# current_sense.net
KiCad netlist of a schematic drawn in Altium Designer
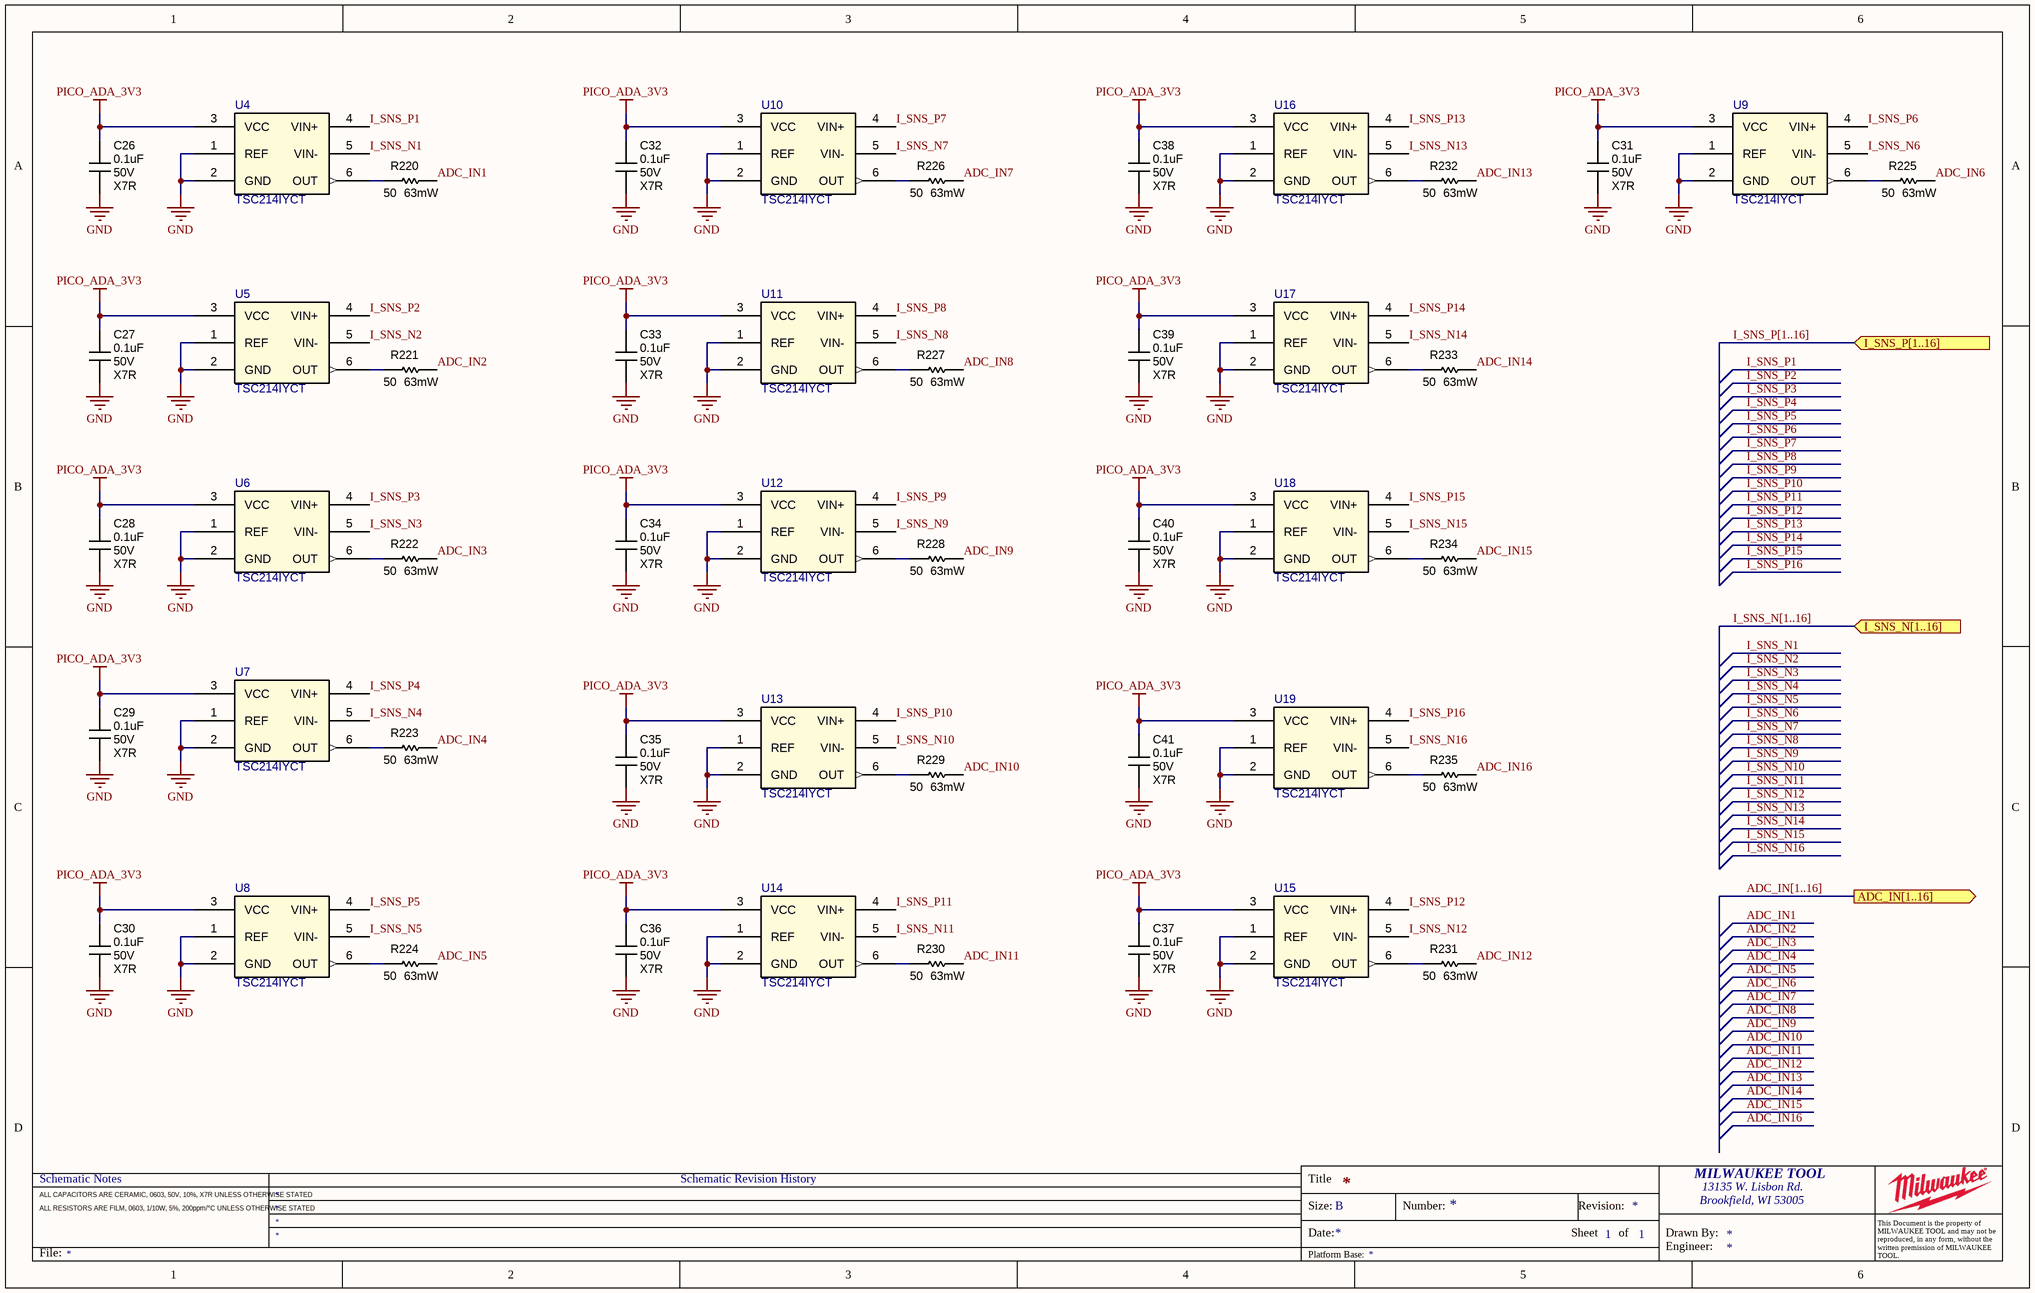
[diagram p0: current_sense.SchDoc]

(export (version "E")
  (design (tool "Eeschema 10.0.6"))
  (components
    (comp (ref "C26")
      (value "0.1uF")
      (footprint "CAPC1005X06N")
      (description "CAP CER SMD 0.1UF 50V X7R 0402")
      (fields
        (field (name "TOLERANCE") "10%")
        (field (name "MFR") "Murata Electronics")
        (field (name "VOLTAGE RATING") "50V")
        (field (name "TEMP COEFF") "X7R")
      )
      (libsource (lib "General_Library") (part "CMP-004-0076"))
    )
    (comp (ref "C27")
      (value "0.1uF")
      (footprint "CAPC1005X06N")
      (description "CAP CER SMD 0.1UF 50V X7R 0402")
      (fields
        (field (name "TOLERANCE") "10%")
        (field (name "MFR") "Murata Electronics")
        (field (name "VOLTAGE RATING") "50V")
        (field (name "TEMP COEFF") "X7R")
      )
      (libsource (lib "General_Library") (part "CMP-004-0076"))
    )
    (comp (ref "C28")
      (value "0.1uF")
      (footprint "CAPC1005X06N")
      (description "CAP CER SMD 0.1UF 50V X7R 0402")
      (fields
        (field (name "TOLERANCE") "10%")
        (field (name "MFR") "Murata Electronics")
        (field (name "VOLTAGE RATING") "50V")
        (field (name "TEMP COEFF") "X7R")
      )
      (libsource (lib "General_Library") (part "CMP-004-0076"))
    )
    (comp (ref "C29")
      (value "0.1uF")
      (footprint "CAPC1005X06N")
      (description "CAP CER SMD 0.1UF 50V X7R 0402")
      (fields
        (field (name "TOLERANCE") "10%")
        (field (name "MFR") "Murata Electronics")
        (field (name "VOLTAGE RATING") "50V")
        (field (name "TEMP COEFF") "X7R")
      )
      (libsource (lib "General_Library") (part "CMP-004-0076"))
    )
    (comp (ref "C30")
      (value "0.1uF")
      (footprint "CAPC1005X06N")
      (description "CAP CER SMD 0.1UF 50V X7R 0402")
      (fields
        (field (name "TOLERANCE") "10%")
        (field (name "MFR") "Murata Electronics")
        (field (name "VOLTAGE RATING") "50V")
        (field (name "TEMP COEFF") "X7R")
      )
      (libsource (lib "General_Library") (part "CMP-004-0076"))
    )
    (comp (ref "C31")
      (value "0.1uF")
      (footprint "CAPC1005X06N")
      (description "CAP CER SMD 0.1UF 50V X7R 0402")
      (fields
        (field (name "TOLERANCE") "10%")
        (field (name "MFR") "Murata Electronics")
        (field (name "VOLTAGE RATING") "50V")
        (field (name "TEMP COEFF") "X7R")
      )
      (libsource (lib "General_Library") (part "CMP-004-0076"))
    )
    (comp (ref "C32")
      (value "0.1uF")
      (footprint "CAPC1005X06N")
      (description "CAP CER SMD 0.1UF 50V X7R 0402")
      (fields
        (field (name "TOLERANCE") "10%")
        (field (name "MFR") "Murata Electronics")
        (field (name "VOLTAGE RATING") "50V")
        (field (name "TEMP COEFF") "X7R")
      )
      (libsource (lib "General_Library") (part "CMP-004-0076"))
    )
    (comp (ref "C33")
      (value "0.1uF")
      (footprint "CAPC1005X06N")
      (description "CAP CER SMD 0.1UF 50V X7R 0402")
      (fields
        (field (name "TOLERANCE") "10%")
        (field (name "MFR") "Murata Electronics")
        (field (name "VOLTAGE RATING") "50V")
        (field (name "TEMP COEFF") "X7R")
      )
      (libsource (lib "General_Library") (part "CMP-004-0076"))
    )
    (comp (ref "C34")
      (value "0.1uF")
      (footprint "CAPC1005X06N")
      (description "CAP CER SMD 0.1UF 50V X7R 0402")
      (fields
        (field (name "TOLERANCE") "10%")
        (field (name "MFR") "Murata Electronics")
        (field (name "VOLTAGE RATING") "50V")
        (field (name "TEMP COEFF") "X7R")
      )
      (libsource (lib "General_Library") (part "CMP-004-0076"))
    )
    (comp (ref "C35")
      (value "0.1uF")
      (footprint "CAPC1005X06N")
      (description "CAP CER SMD 0.1UF 50V X7R 0402")
      (fields
        (field (name "TOLERANCE") "10%")
        (field (name "MFR") "Murata Electronics")
        (field (name "VOLTAGE RATING") "50V")
        (field (name "TEMP COEFF") "X7R")
      )
      (libsource (lib "General_Library") (part "CMP-004-0076"))
    )
    (comp (ref "C36")
      (value "0.1uF")
      (footprint "CAPC1005X06N")
      (description "CAP CER SMD 0.1UF 50V X7R 0402")
      (fields
        (field (name "TOLERANCE") "10%")
        (field (name "MFR") "Murata Electronics")
        (field (name "VOLTAGE RATING") "50V")
        (field (name "TEMP COEFF") "X7R")
      )
      (libsource (lib "General_Library") (part "CMP-004-0076"))
    )
    (comp (ref "C37")
      (value "0.1uF")
      (footprint "CAPC1005X06N")
      (description "CAP CER SMD 0.1UF 50V X7R 0402")
      (fields
        (field (name "TOLERANCE") "10%")
        (field (name "MFR") "Murata Electronics")
        (field (name "VOLTAGE RATING") "50V")
        (field (name "TEMP COEFF") "X7R")
      )
      (libsource (lib "General_Library") (part "CMP-004-0076"))
    )
    (comp (ref "C38")
      (value "0.1uF")
      (footprint "CAPC1005X06N")
      (description "CAP CER SMD 0.1UF 50V X7R 0402")
      (fields
        (field (name "TOLERANCE") "10%")
        (field (name "MFR") "Murata Electronics")
        (field (name "VOLTAGE RATING") "50V")
        (field (name "TEMP COEFF") "X7R")
      )
      (libsource (lib "General_Library") (part "CMP-004-0076"))
    )
    (comp (ref "C39")
      (value "0.1uF")
      (footprint "CAPC1005X06N")
      (description "CAP CER SMD 0.1UF 50V X7R 0402")
      (fields
        (field (name "TOLERANCE") "10%")
        (field (name "MFR") "Murata Electronics")
        (field (name "VOLTAGE RATING") "50V")
        (field (name "TEMP COEFF") "X7R")
      )
      (libsource (lib "General_Library") (part "CMP-004-0076"))
    )
    (comp (ref "C40")
      (value "0.1uF")
      (footprint "CAPC1005X06N")
      (description "CAP CER SMD 0.1UF 50V X7R 0402")
      (fields
        (field (name "TOLERANCE") "10%")
        (field (name "MFR") "Murata Electronics")
        (field (name "VOLTAGE RATING") "50V")
        (field (name "TEMP COEFF") "X7R")
      )
      (libsource (lib "General_Library") (part "CMP-004-0076"))
    )
    (comp (ref "C41")
      (value "0.1uF")
      (footprint "CAPC1005X06N")
      (description "CAP CER SMD 0.1UF 50V X7R 0402")
      (fields
        (field (name "TOLERANCE") "10%")
        (field (name "MFR") "Murata Electronics")
        (field (name "VOLTAGE RATING") "50V")
        (field (name "TEMP COEFF") "X7R")
      )
      (libsource (lib "General_Library") (part "CMP-004-0076"))
    )
    (comp (ref "R220")
      (value "50")
      (footprint "RESC1005X04N")
      (description "RES SMD 50R OHM 1% 1/16W 0402")
      (fields
        (field (name "TOLERANCE") "1%")
        (field (name "MFR") "KOA Speer Electronics")
        (field (name "WATTAGE") "63mW")
      )
      (libsource (lib "General_Library") (part "CMP-025-0174"))
    )
    (comp (ref "R221")
      (value "50")
      (footprint "RESC1005X04N")
      (description "RES SMD 50R OHM 1% 1/16W 0402")
      (fields
        (field (name "TOLERANCE") "1%")
        (field (name "MFR") "KOA Speer Electronics")
        (field (name "WATTAGE") "63mW")
      )
      (libsource (lib "General_Library") (part "CMP-025-0174"))
    )
    (comp (ref "R222")
      (value "50")
      (footprint "RESC1005X04N")
      (description "RES SMD 50R OHM 1% 1/16W 0402")
      (fields
        (field (name "TOLERANCE") "1%")
        (field (name "MFR") "KOA Speer Electronics")
        (field (name "WATTAGE") "63mW")
      )
      (libsource (lib "General_Library") (part "CMP-025-0174"))
    )
    (comp (ref "R223")
      (value "50")
      (footprint "RESC1005X04N")
      (description "RES SMD 50R OHM 1% 1/16W 0402")
      (fields
        (field (name "TOLERANCE") "1%")
        (field (name "MFR") "KOA Speer Electronics")
        (field (name "WATTAGE") "63mW")
      )
      (libsource (lib "General_Library") (part "CMP-025-0174"))
    )
    (comp (ref "R224")
      (value "50")
      (footprint "RESC1005X04N")
      (description "RES SMD 50R OHM 1% 1/16W 0402")
      (fields
        (field (name "TOLERANCE") "1%")
        (field (name "MFR") "KOA Speer Electronics")
        (field (name "WATTAGE") "63mW")
      )
      (libsource (lib "General_Library") (part "CMP-025-0174"))
    )
    (comp (ref "R225")
      (value "50")
      (footprint "RESC1005X04N")
      (description "RES SMD 50R OHM 1% 1/16W 0402")
      (fields
        (field (name "TOLERANCE") "1%")
        (field (name "MFR") "KOA Speer Electronics")
        (field (name "WATTAGE") "63mW")
      )
      (libsource (lib "General_Library") (part "CMP-025-0174"))
    )
    (comp (ref "R226")
      (value "50")
      (footprint "RESC1005X04N")
      (description "RES SMD 50R OHM 1% 1/16W 0402")
      (fields
        (field (name "TOLERANCE") "1%")
        (field (name "MFR") "KOA Speer Electronics")
        (field (name "WATTAGE") "63mW")
      )
      (libsource (lib "General_Library") (part "CMP-025-0174"))
    )
    (comp (ref "R227")
      (value "50")
      (footprint "RESC1005X04N")
      (description "RES SMD 50R OHM 1% 1/16W 0402")
      (fields
        (field (name "TOLERANCE") "1%")
        (field (name "MFR") "KOA Speer Electronics")
        (field (name "WATTAGE") "63mW")
      )
      (libsource (lib "General_Library") (part "CMP-025-0174"))
    )
    (comp (ref "R228")
      (value "50")
      (footprint "RESC1005X04N")
      (description "RES SMD 50R OHM 1% 1/16W 0402")
      (fields
        (field (name "TOLERANCE") "1%")
        (field (name "MFR") "KOA Speer Electronics")
        (field (name "WATTAGE") "63mW")
      )
      (libsource (lib "General_Library") (part "CMP-025-0174"))
    )
    (comp (ref "R229")
      (value "50")
      (footprint "RESC1005X04N")
      (description "RES SMD 50R OHM 1% 1/16W 0402")
      (fields
        (field (name "TOLERANCE") "1%")
        (field (name "MFR") "KOA Speer Electronics")
        (field (name "WATTAGE") "63mW")
      )
      (libsource (lib "General_Library") (part "CMP-025-0174"))
    )
    (comp (ref "R230")
      (value "50")
      (footprint "RESC1005X04N")
      (description "RES SMD 50R OHM 1% 1/16W 0402")
      (fields
        (field (name "TOLERANCE") "1%")
        (field (name "MFR") "KOA Speer Electronics")
        (field (name "WATTAGE") "63mW")
      )
      (libsource (lib "General_Library") (part "CMP-025-0174"))
    )
    (comp (ref "R231")
      (value "50")
      (footprint "RESC1005X04N")
      (description "RES SMD 50R OHM 1% 1/16W 0402")
      (fields
        (field (name "TOLERANCE") "1%")
        (field (name "MFR") "KOA Speer Electronics")
        (field (name "WATTAGE") "63mW")
      )
      (libsource (lib "General_Library") (part "CMP-025-0174"))
    )
    (comp (ref "R232")
      (value "50")
      (footprint "RESC1005X04N")
      (description "RES SMD 50R OHM 1% 1/16W 0402")
      (fields
        (field (name "TOLERANCE") "1%")
        (field (name "MFR") "KOA Speer Electronics")
        (field (name "WATTAGE") "63mW")
      )
      (libsource (lib "General_Library") (part "CMP-025-0174"))
    )
    (comp (ref "R233")
      (value "50")
      (footprint "RESC1005X04N")
      (description "RES SMD 50R OHM 1% 1/16W 0402")
      (fields
        (field (name "TOLERANCE") "1%")
        (field (name "MFR") "KOA Speer Electronics")
        (field (name "WATTAGE") "63mW")
      )
      (libsource (lib "General_Library") (part "CMP-025-0174"))
    )
    (comp (ref "R234")
      (value "50")
      (footprint "RESC1005X04N")
      (description "RES SMD 50R OHM 1% 1/16W 0402")
      (fields
        (field (name "TOLERANCE") "1%")
        (field (name "MFR") "KOA Speer Electronics")
        (field (name "WATTAGE") "63mW")
      )
      (libsource (lib "General_Library") (part "CMP-025-0174"))
    )
    (comp (ref "R235")
      (value "50")
      (footprint "RESC1005X04N")
      (description "RES SMD 50R OHM 1% 1/16W 0402")
      (fields
        (field (name "TOLERANCE") "1%")
        (field (name "MFR") "KOA Speer Electronics")
        (field (name "WATTAGE") "63mW")
      )
      (libsource (lib "General_Library") (part "CMP-025-0174"))
    )
    (comp (ref "U4")
      (value "TSC214IYCT")
      (footprint "Footprints:SOT65P210X110-6N")
      (description "IC CURR SENSE 1 CIRCUIT SC70-6")
      (fields (field (name "MFR") "STMicroelectronics"))
      (libsource (lib "Symbols") (part "CMP-017-0113"))
    )
    (comp (ref "U5")
      (value "TSC214IYCT")
      (footprint "Footprints:SOT65P210X110-6N")
      (description "IC CURR SENSE 1 CIRCUIT SC70-6")
      (fields (field (name "MFR") "STMicroelectronics"))
      (libsource (lib "Symbols") (part "CMP-017-0113"))
    )
    (comp (ref "U6")
      (value "TSC214IYCT")
      (footprint "Footprints:SOT65P210X110-6N")
      (description "IC CURR SENSE 1 CIRCUIT SC70-6")
      (fields (field (name "MFR") "STMicroelectronics"))
      (libsource (lib "Symbols") (part "CMP-017-0113"))
    )
    (comp (ref "U7")
      (value "TSC214IYCT")
      (footprint "Footprints:SOT65P210X110-6N")
      (description "IC CURR SENSE 1 CIRCUIT SC70-6")
      (fields (field (name "MFR") "STMicroelectronics"))
      (libsource (lib "Symbols") (part "CMP-017-0113"))
    )
    (comp (ref "U8")
      (value "TSC214IYCT")
      (footprint "Footprints:SOT65P210X110-6N")
      (description "IC CURR SENSE 1 CIRCUIT SC70-6")
      (fields (field (name "MFR") "STMicroelectronics"))
      (libsource (lib "Symbols") (part "CMP-017-0113"))
    )
    (comp (ref "U9")
      (value "TSC214IYCT")
      (footprint "Footprints:SOT65P210X110-6N")
      (description "IC CURR SENSE 1 CIRCUIT SC70-6")
      (fields (field (name "MFR") "STMicroelectronics"))
      (libsource (lib "Symbols") (part "CMP-017-0113"))
    )
    (comp (ref "U10")
      (value "TSC214IYCT")
      (footprint "Footprints:SOT65P210X110-6N")
      (description "IC CURR SENSE 1 CIRCUIT SC70-6")
      (fields (field (name "MFR") "STMicroelectronics"))
      (libsource (lib "Symbols") (part "CMP-017-0113"))
    )
    (comp (ref "U11")
      (value "TSC214IYCT")
      (footprint "Footprints:SOT65P210X110-6N")
      (description "IC CURR SENSE 1 CIRCUIT SC70-6")
      (fields (field (name "MFR") "STMicroelectronics"))
      (libsource (lib "Symbols") (part "CMP-017-0113"))
    )
    (comp (ref "U12")
      (value "TSC214IYCT")
      (footprint "Footprints:SOT65P210X110-6N")
      (description "IC CURR SENSE 1 CIRCUIT SC70-6")
      (fields (field (name "MFR") "STMicroelectronics"))
      (libsource (lib "Symbols") (part "CMP-017-0113"))
    )
    (comp (ref "U13")
      (value "TSC214IYCT")
      (footprint "Footprints:SOT65P210X110-6N")
      (description "IC CURR SENSE 1 CIRCUIT SC70-6")
      (fields (field (name "MFR") "STMicroelectronics"))
      (libsource (lib "Symbols") (part "CMP-017-0113"))
    )
    (comp (ref "U14")
      (value "TSC214IYCT")
      (footprint "Footprints:SOT65P210X110-6N")
      (description "IC CURR SENSE 1 CIRCUIT SC70-6")
      (fields (field (name "MFR") "STMicroelectronics"))
      (libsource (lib "Symbols") (part "CMP-017-0113"))
    )
    (comp (ref "U15")
      (value "TSC214IYCT")
      (footprint "Footprints:SOT65P210X110-6N")
      (description "IC CURR SENSE 1 CIRCUIT SC70-6")
      (fields (field (name "MFR") "STMicroelectronics"))
      (libsource (lib "Symbols") (part "CMP-017-0113"))
    )
    (comp (ref "U16")
      (value "TSC214IYCT")
      (footprint "Footprints:SOT65P210X110-6N")
      (description "IC CURR SENSE 1 CIRCUIT SC70-6")
      (fields (field (name "MFR") "STMicroelectronics"))
      (libsource (lib "Symbols") (part "CMP-017-0113"))
    )
    (comp (ref "U17")
      (value "TSC214IYCT")
      (footprint "Footprints:SOT65P210X110-6N")
      (description "IC CURR SENSE 1 CIRCUIT SC70-6")
      (fields (field (name "MFR") "STMicroelectronics"))
      (libsource (lib "Symbols") (part "CMP-017-0113"))
    )
    (comp (ref "U18")
      (value "TSC214IYCT")
      (footprint "Footprints:SOT65P210X110-6N")
      (description "IC CURR SENSE 1 CIRCUIT SC70-6")
      (fields (field (name "MFR") "STMicroelectronics"))
      (libsource (lib "Symbols") (part "CMP-017-0113"))
    )
    (comp (ref "U19")
      (value "TSC214IYCT")
      (footprint "Footprints:SOT65P210X110-6N")
      (description "IC CURR SENSE 1 CIRCUIT SC70-6")
      (fields (field (name "MFR") "STMicroelectronics"))
      (libsource (lib "Symbols") (part "CMP-017-0113"))
    )
  )
  (nets
    (net (code "1") (name "/ADC_IN1") (class "Default")
      (node (ref "R220") (pin "2") (pinfunction "2_2") (pintype "passive"))
    )
    (net (code "2") (name "/ADC_IN2") (class "Default")
      (node (ref "R221") (pin "2") (pinfunction "2_2") (pintype "passive"))
    )
    (net (code "3") (name "/ADC_IN3") (class "Default")
      (node (ref "R222") (pin "2") (pinfunction "2_2") (pintype "passive"))
    )
    (net (code "4") (name "/ADC_IN4") (class "Default")
      (node (ref "R223") (pin "2") (pinfunction "2_2") (pintype "passive"))
    )
    (net (code "5") (name "/ADC_IN5") (class "Default")
      (node (ref "R224") (pin "2") (pinfunction "2_2") (pintype "passive"))
    )
    (net (code "6") (name "/ADC_IN6") (class "Default")
      (node (ref "R225") (pin "2") (pinfunction "2_2") (pintype "passive"))
    )
    (net (code "7") (name "/ADC_IN7") (class "Default")
      (node (ref "R226") (pin "2") (pinfunction "2_2") (pintype "passive"))
    )
    (net (code "8") (name "/ADC_IN8") (class "Default")
      (node (ref "R227") (pin "2") (pinfunction "2_2") (pintype "passive"))
    )
    (net (code "9") (name "/ADC_IN9") (class "Default")
      (node (ref "R228") (pin "2") (pinfunction "2_2") (pintype "passive"))
    )
    (net (code "10") (name "/ADC_IN10") (class "Default")
      (node (ref "R229") (pin "2") (pinfunction "2_2") (pintype "passive"))
    )
    (net (code "11") (name "/ADC_IN11") (class "Default")
      (node (ref "R230") (pin "2") (pinfunction "2_2") (pintype "passive"))
    )
    (net (code "12") (name "/ADC_IN12") (class "Default")
      (node (ref "R231") (pin "2") (pinfunction "2_2") (pintype "passive"))
    )
    (net (code "13") (name "/ADC_IN13") (class "Default")
      (node (ref "R232") (pin "2") (pinfunction "2_2") (pintype "passive"))
    )
    (net (code "14") (name "/ADC_IN14") (class "Default")
      (node (ref "R233") (pin "2") (pinfunction "2_2") (pintype "passive"))
    )
    (net (code "15") (name "/ADC_IN15") (class "Default")
      (node (ref "R234") (pin "2") (pinfunction "2_2") (pintype "passive"))
    )
    (net (code "16") (name "/ADC_IN16") (class "Default")
      (node (ref "R235") (pin "2") (pinfunction "2_2") (pintype "passive"))
    )
    (net (code "18") (name "/I_SNS_N1") (class "Default")
      (node (ref "U4") (pin "5") (pinfunction "VIN-_5") (pintype "passive"))
    )
    (net (code "19") (name "/I_SNS_N2") (class "Default")
      (node (ref "U5") (pin "5") (pinfunction "VIN-_5") (pintype "passive"))
    )
    (net (code "20") (name "/I_SNS_N3") (class "Default")
      (node (ref "U6") (pin "5") (pinfunction "VIN-_5") (pintype "passive"))
    )
    (net (code "21") (name "/I_SNS_N4") (class "Default")
      (node (ref "U7") (pin "5") (pinfunction "VIN-_5") (pintype "passive"))
    )
    (net (code "22") (name "/I_SNS_N5") (class "Default")
      (node (ref "U8") (pin "5") (pinfunction "VIN-_5") (pintype "passive"))
    )
    (net (code "23") (name "/I_SNS_N6") (class "Default")
      (node (ref "U9") (pin "5") (pinfunction "VIN-_5") (pintype "passive"))
    )
    (net (code "24") (name "/I_SNS_N7") (class "Default")
      (node (ref "U10") (pin "5") (pinfunction "VIN-_5") (pintype "passive"))
    )
    (net (code "25") (name "/I_SNS_N8") (class "Default")
      (node (ref "U11") (pin "5") (pinfunction "VIN-_5") (pintype "passive"))
    )
    (net (code "26") (name "/I_SNS_N9") (class "Default")
      (node (ref "U12") (pin "5") (pinfunction "VIN-_5") (pintype "passive"))
    )
    (net (code "27") (name "/I_SNS_N10") (class "Default")
      (node (ref "U13") (pin "5") (pinfunction "VIN-_5") (pintype "passive"))
    )
    (net (code "28") (name "/I_SNS_N11") (class "Default")
      (node (ref "U14") (pin "5") (pinfunction "VIN-_5") (pintype "passive"))
    )
    (net (code "29") (name "/I_SNS_N12") (class "Default")
      (node (ref "U15") (pin "5") (pinfunction "VIN-_5") (pintype "passive"))
    )
    (net (code "30") (name "/I_SNS_N13") (class "Default")
      (node (ref "U16") (pin "5") (pinfunction "VIN-_5") (pintype "passive"))
    )
    (net (code "31") (name "/I_SNS_N14") (class "Default")
      (node (ref "U17") (pin "5") (pinfunction "VIN-_5") (pintype "passive"))
    )
    (net (code "32") (name "/I_SNS_N15") (class "Default")
      (node (ref "U18") (pin "5") (pinfunction "VIN-_5") (pintype "passive"))
    )
    (net (code "33") (name "/I_SNS_N16") (class "Default")
      (node (ref "U19") (pin "5") (pinfunction "VIN-_5") (pintype "passive"))
    )
    (net (code "35") (name "/I_SNS_P1") (class "Default")
      (node (ref "U4") (pin "4") (pinfunction "VIN+_4") (pintype "passive"))
    )
    (net (code "36") (name "/I_SNS_P2") (class "Default")
      (node (ref "U5") (pin "4") (pinfunction "VIN+_4") (pintype "passive"))
    )
    (net (code "37") (name "/I_SNS_P3") (class "Default")
      (node (ref "U6") (pin "4") (pinfunction "VIN+_4") (pintype "passive"))
    )
    (net (code "38") (name "/I_SNS_P4") (class "Default")
      (node (ref "U7") (pin "4") (pinfunction "VIN+_4") (pintype "passive"))
    )
    (net (code "39") (name "/I_SNS_P5") (class "Default")
      (node (ref "U8") (pin "4") (pinfunction "VIN+_4") (pintype "passive"))
    )
    (net (code "40") (name "/I_SNS_P6") (class "Default")
      (node (ref "U9") (pin "4") (pinfunction "VIN+_4") (pintype "passive"))
    )
    (net (code "41") (name "/I_SNS_P7") (class "Default")
      (node (ref "U10") (pin "4") (pinfunction "VIN+_4") (pintype "passive"))
    )
    (net (code "42") (name "/I_SNS_P8") (class "Default")
      (node (ref "U11") (pin "4") (pinfunction "VIN+_4") (pintype "passive"))
    )
    (net (code "43") (name "/I_SNS_P9") (class "Default")
      (node (ref "U12") (pin "4") (pinfunction "VIN+_4") (pintype "passive"))
    )
    (net (code "44") (name "/I_SNS_P10") (class "Default")
      (node (ref "U13") (pin "4") (pinfunction "VIN+_4") (pintype "passive"))
    )
    (net (code "45") (name "/I_SNS_P11") (class "Default")
      (node (ref "U14") (pin "4") (pinfunction "VIN+_4") (pintype "passive"))
    )
    (net (code "46") (name "/I_SNS_P12") (class "Default")
      (node (ref "U15") (pin "4") (pinfunction "VIN+_4") (pintype "passive"))
    )
    (net (code "47") (name "/I_SNS_P13") (class "Default")
      (node (ref "U16") (pin "4") (pinfunction "VIN+_4") (pintype "passive"))
    )
    (net (code "48") (name "/I_SNS_P14") (class "Default")
      (node (ref "U17") (pin "4") (pinfunction "VIN+_4") (pintype "passive"))
    )
    (net (code "49") (name "/I_SNS_P15") (class "Default")
      (node (ref "U18") (pin "4") (pinfunction "VIN+_4") (pintype "passive"))
    )
    (net (code "50") (name "/I_SNS_P16") (class "Default")
      (node (ref "U19") (pin "4") (pinfunction "VIN+_4") (pintype "passive"))
    )
    (net (code "52") (name "GND") (class "Default")
      (node (ref "C26") (pin "2") (pinfunction "2_2") (pintype "passive"))
      (node (ref "C27") (pin "2") (pinfunction "2_2") (pintype "passive"))
      (node (ref "C28") (pin "2") (pinfunction "2_2") (pintype "passive"))
      (node (ref "C29") (pin "2") (pinfunction "2_2") (pintype "passive"))
      (node (ref "C30") (pin "2") (pinfunction "2_2") (pintype "passive"))
      (node (ref "C31") (pin "2") (pinfunction "2_2") (pintype "passive"))
      (node (ref "C32") (pin "2") (pinfunction "2_2") (pintype "passive"))
      (node (ref "C33") (pin "2") (pinfunction "2_2") (pintype "passive"))
      (node (ref "C34") (pin "2") (pinfunction "2_2") (pintype "passive"))
      (node (ref "C35") (pin "2") (pinfunction "2_2") (pintype "passive"))
      (node (ref "C36") (pin "2") (pinfunction "2_2") (pintype "passive"))
      (node (ref "C37") (pin "2") (pinfunction "2_2") (pintype "passive"))
      (node (ref "C38") (pin "2") (pinfunction "2_2") (pintype "passive"))
      (node (ref "C39") (pin "2") (pinfunction "2_2") (pintype "passive"))
      (node (ref "C40") (pin "2") (pinfunction "2_2") (pintype "passive"))
      (node (ref "C41") (pin "2") (pinfunction "2_2") (pintype "passive"))
      (node (ref "U10") (pin "1") (pinfunction "REF_1") (pintype "passive"))
      (node (ref "U10") (pin "2") (pinfunction "GND_2") (pintype "power_in"))
      (node (ref "U11") (pin "1") (pinfunction "REF_1") (pintype "passive"))
      (node (ref "U11") (pin "2") (pinfunction "GND_2") (pintype "power_in"))
      (node (ref "U12") (pin "1") (pinfunction "REF_1") (pintype "passive"))
      (node (ref "U12") (pin "2") (pinfunction "GND_2") (pintype "power_in"))
      (node (ref "U13") (pin "1") (pinfunction "REF_1") (pintype "passive"))
      (node (ref "U13") (pin "2") (pinfunction "GND_2") (pintype "power_in"))
      (node (ref "U14") (pin "1") (pinfunction "REF_1") (pintype "passive"))
      (node (ref "U14") (pin "2") (pinfunction "GND_2") (pintype "power_in"))
      (node (ref "U15") (pin "1") (pinfunction "REF_1") (pintype "passive"))
      (node (ref "U15") (pin "2") (pinfunction "GND_2") (pintype "power_in"))
      (node (ref "U16") (pin "1") (pinfunction "REF_1") (pintype "passive"))
      (node (ref "U16") (pin "2") (pinfunction "GND_2") (pintype "power_in"))
      (node (ref "U17") (pin "1") (pinfunction "REF_1") (pintype "passive"))
      (node (ref "U17") (pin "2") (pinfunction "GND_2") (pintype "power_in"))
      (node (ref "U18") (pin "1") (pinfunction "REF_1") (pintype "passive"))
      (node (ref "U18") (pin "2") (pinfunction "GND_2") (pintype "power_in"))
      (node (ref "U19") (pin "1") (pinfunction "REF_1") (pintype "passive"))
      (node (ref "U19") (pin "2") (pinfunction "GND_2") (pintype "power_in"))
      (node (ref "U4") (pin "1") (pinfunction "REF_1") (pintype "passive"))
      (node (ref "U4") (pin "2") (pinfunction "GND_2") (pintype "power_in"))
      (node (ref "U5") (pin "1") (pinfunction "REF_1") (pintype "passive"))
      (node (ref "U5") (pin "2") (pinfunction "GND_2") (pintype "power_in"))
      (node (ref "U6") (pin "1") (pinfunction "REF_1") (pintype "passive"))
      (node (ref "U6") (pin "2") (pinfunction "GND_2") (pintype "power_in"))
      (node (ref "U7") (pin "1") (pinfunction "REF_1") (pintype "passive"))
      (node (ref "U7") (pin "2") (pinfunction "GND_2") (pintype "power_in"))
      (node (ref "U8") (pin "1") (pinfunction "REF_1") (pintype "passive"))
      (node (ref "U8") (pin "2") (pinfunction "GND_2") (pintype "power_in"))
      (node (ref "U9") (pin "1") (pinfunction "REF_1") (pintype "passive"))
      (node (ref "U9") (pin "2") (pinfunction "GND_2") (pintype "power_in"))
    )
    (net (code "53") (name "Net-(U4-OUT)") (class "Default")
      (node (ref "R220") (pin "1") (pinfunction "1_1") (pintype "passive"))
      (node (ref "U4") (pin "6") (pinfunction "OUT_6") (pintype "output"))
    )
    (net (code "54") (name "Net-(U5-OUT)") (class "Default")
      (node (ref "R221") (pin "1") (pinfunction "1_1") (pintype "passive"))
      (node (ref "U5") (pin "6") (pinfunction "OUT_6") (pintype "output"))
    )
    (net (code "55") (name "Net-(U6-OUT)") (class "Default")
      (node (ref "R222") (pin "1") (pinfunction "1_1") (pintype "passive"))
      (node (ref "U6") (pin "6") (pinfunction "OUT_6") (pintype "output"))
    )
    (net (code "56") (name "Net-(U7-OUT)") (class "Default")
      (node (ref "R223") (pin "1") (pinfunction "1_1") (pintype "passive"))
      (node (ref "U7") (pin "6") (pinfunction "OUT_6") (pintype "output"))
    )
    (net (code "57") (name "Net-(U8-OUT)") (class "Default")
      (node (ref "R224") (pin "1") (pinfunction "1_1") (pintype "passive"))
      (node (ref "U8") (pin "6") (pinfunction "OUT_6") (pintype "output"))
    )
    (net (code "58") (name "Net-(U9-OUT)") (class "Default")
      (node (ref "R225") (pin "1") (pinfunction "1_1") (pintype "passive"))
      (node (ref "U9") (pin "6") (pinfunction "OUT_6") (pintype "output"))
    )
    (net (code "59") (name "Net-(U10-OUT)") (class "Default")
      (node (ref "R226") (pin "1") (pinfunction "1_1") (pintype "passive"))
      (node (ref "U10") (pin "6") (pinfunction "OUT_6") (pintype "output"))
    )
    (net (code "60") (name "Net-(U11-OUT)") (class "Default")
      (node (ref "R227") (pin "1") (pinfunction "1_1") (pintype "passive"))
      (node (ref "U11") (pin "6") (pinfunction "OUT_6") (pintype "output"))
    )
    (net (code "61") (name "Net-(U12-OUT)") (class "Default")
      (node (ref "R228") (pin "1") (pinfunction "1_1") (pintype "passive"))
      (node (ref "U12") (pin "6") (pinfunction "OUT_6") (pintype "output"))
    )
    (net (code "62") (name "Net-(U13-OUT)") (class "Default")
      (node (ref "R229") (pin "1") (pinfunction "1_1") (pintype "passive"))
      (node (ref "U13") (pin "6") (pinfunction "OUT_6") (pintype "output"))
    )
    (net (code "63") (name "Net-(U14-OUT)") (class "Default")
      (node (ref "R230") (pin "1") (pinfunction "1_1") (pintype "passive"))
      (node (ref "U14") (pin "6") (pinfunction "OUT_6") (pintype "output"))
    )
    (net (code "64") (name "Net-(U15-OUT)") (class "Default")
      (node (ref "R231") (pin "1") (pinfunction "1_1") (pintype "passive"))
      (node (ref "U15") (pin "6") (pinfunction "OUT_6") (pintype "output"))
    )
    (net (code "65") (name "Net-(U16-OUT)") (class "Default")
      (node (ref "R232") (pin "1") (pinfunction "1_1") (pintype "passive"))
      (node (ref "U16") (pin "6") (pinfunction "OUT_6") (pintype "output"))
    )
    (net (code "66") (name "Net-(U17-OUT)") (class "Default")
      (node (ref "R233") (pin "1") (pinfunction "1_1") (pintype "passive"))
      (node (ref "U17") (pin "6") (pinfunction "OUT_6") (pintype "output"))
    )
    (net (code "67") (name "Net-(U18-OUT)") (class "Default")
      (node (ref "R234") (pin "1") (pinfunction "1_1") (pintype "passive"))
      (node (ref "U18") (pin "6") (pinfunction "OUT_6") (pintype "output"))
    )
    (net (code "68") (name "Net-(U19-OUT)") (class "Default")
      (node (ref "R235") (pin "1") (pinfunction "1_1") (pintype "passive"))
      (node (ref "U19") (pin "6") (pinfunction "OUT_6") (pintype "output"))
    )
    (net (code "69") (name "PICO_ADA_3V3") (class "Default")
      (node (ref "C26") (pin "1") (pinfunction "1_1") (pintype "passive"))
      (node (ref "C27") (pin "1") (pinfunction "1_1") (pintype "passive"))
      (node (ref "C28") (pin "1") (pinfunction "1_1") (pintype "passive"))
      (node (ref "C29") (pin "1") (pinfunction "1_1") (pintype "passive"))
      (node (ref "C30") (pin "1") (pinfunction "1_1") (pintype "passive"))
      (node (ref "C31") (pin "1") (pinfunction "1_1") (pintype "passive"))
      (node (ref "C32") (pin "1") (pinfunction "1_1") (pintype "passive"))
      (node (ref "C33") (pin "1") (pinfunction "1_1") (pintype "passive"))
      (node (ref "C34") (pin "1") (pinfunction "1_1") (pintype "passive"))
      (node (ref "C35") (pin "1") (pinfunction "1_1") (pintype "passive"))
      (node (ref "C36") (pin "1") (pinfunction "1_1") (pintype "passive"))
      (node (ref "C37") (pin "1") (pinfunction "1_1") (pintype "passive"))
      (node (ref "C38") (pin "1") (pinfunction "1_1") (pintype "passive"))
      (node (ref "C39") (pin "1") (pinfunction "1_1") (pintype "passive"))
      (node (ref "C40") (pin "1") (pinfunction "1_1") (pintype "passive"))
      (node (ref "C41") (pin "1") (pinfunction "1_1") (pintype "passive"))
      (node (ref "U10") (pin "3") (pinfunction "VCC_3") (pintype "power_in"))
      (node (ref "U11") (pin "3") (pinfunction "VCC_3") (pintype "power_in"))
      (node (ref "U12") (pin "3") (pinfunction "VCC_3") (pintype "power_in"))
      (node (ref "U13") (pin "3") (pinfunction "VCC_3") (pintype "power_in"))
      (node (ref "U14") (pin "3") (pinfunction "VCC_3") (pintype "power_in"))
      (node (ref "U15") (pin "3") (pinfunction "VCC_3") (pintype "power_in"))
      (node (ref "U16") (pin "3") (pinfunction "VCC_3") (pintype "power_in"))
      (node (ref "U17") (pin "3") (pinfunction "VCC_3") (pintype "power_in"))
      (node (ref "U18") (pin "3") (pinfunction "VCC_3") (pintype "power_in"))
      (node (ref "U19") (pin "3") (pinfunction "VCC_3") (pintype "power_in"))
      (node (ref "U4") (pin "3") (pinfunction "VCC_3") (pintype "power_in"))
      (node (ref "U5") (pin "3") (pinfunction "VCC_3") (pintype "power_in"))
      (node (ref "U6") (pin "3") (pinfunction "VCC_3") (pintype "power_in"))
      (node (ref "U7") (pin "3") (pinfunction "VCC_3") (pintype "power_in"))
      (node (ref "U8") (pin "3") (pinfunction "VCC_3") (pintype "power_in"))
      (node (ref "U9") (pin "3") (pinfunction "VCC_3") (pintype "power_in"))
    )
  )
)
